# W5500_shield.net
KiCad netlist of a schematic drawn in EAGLE
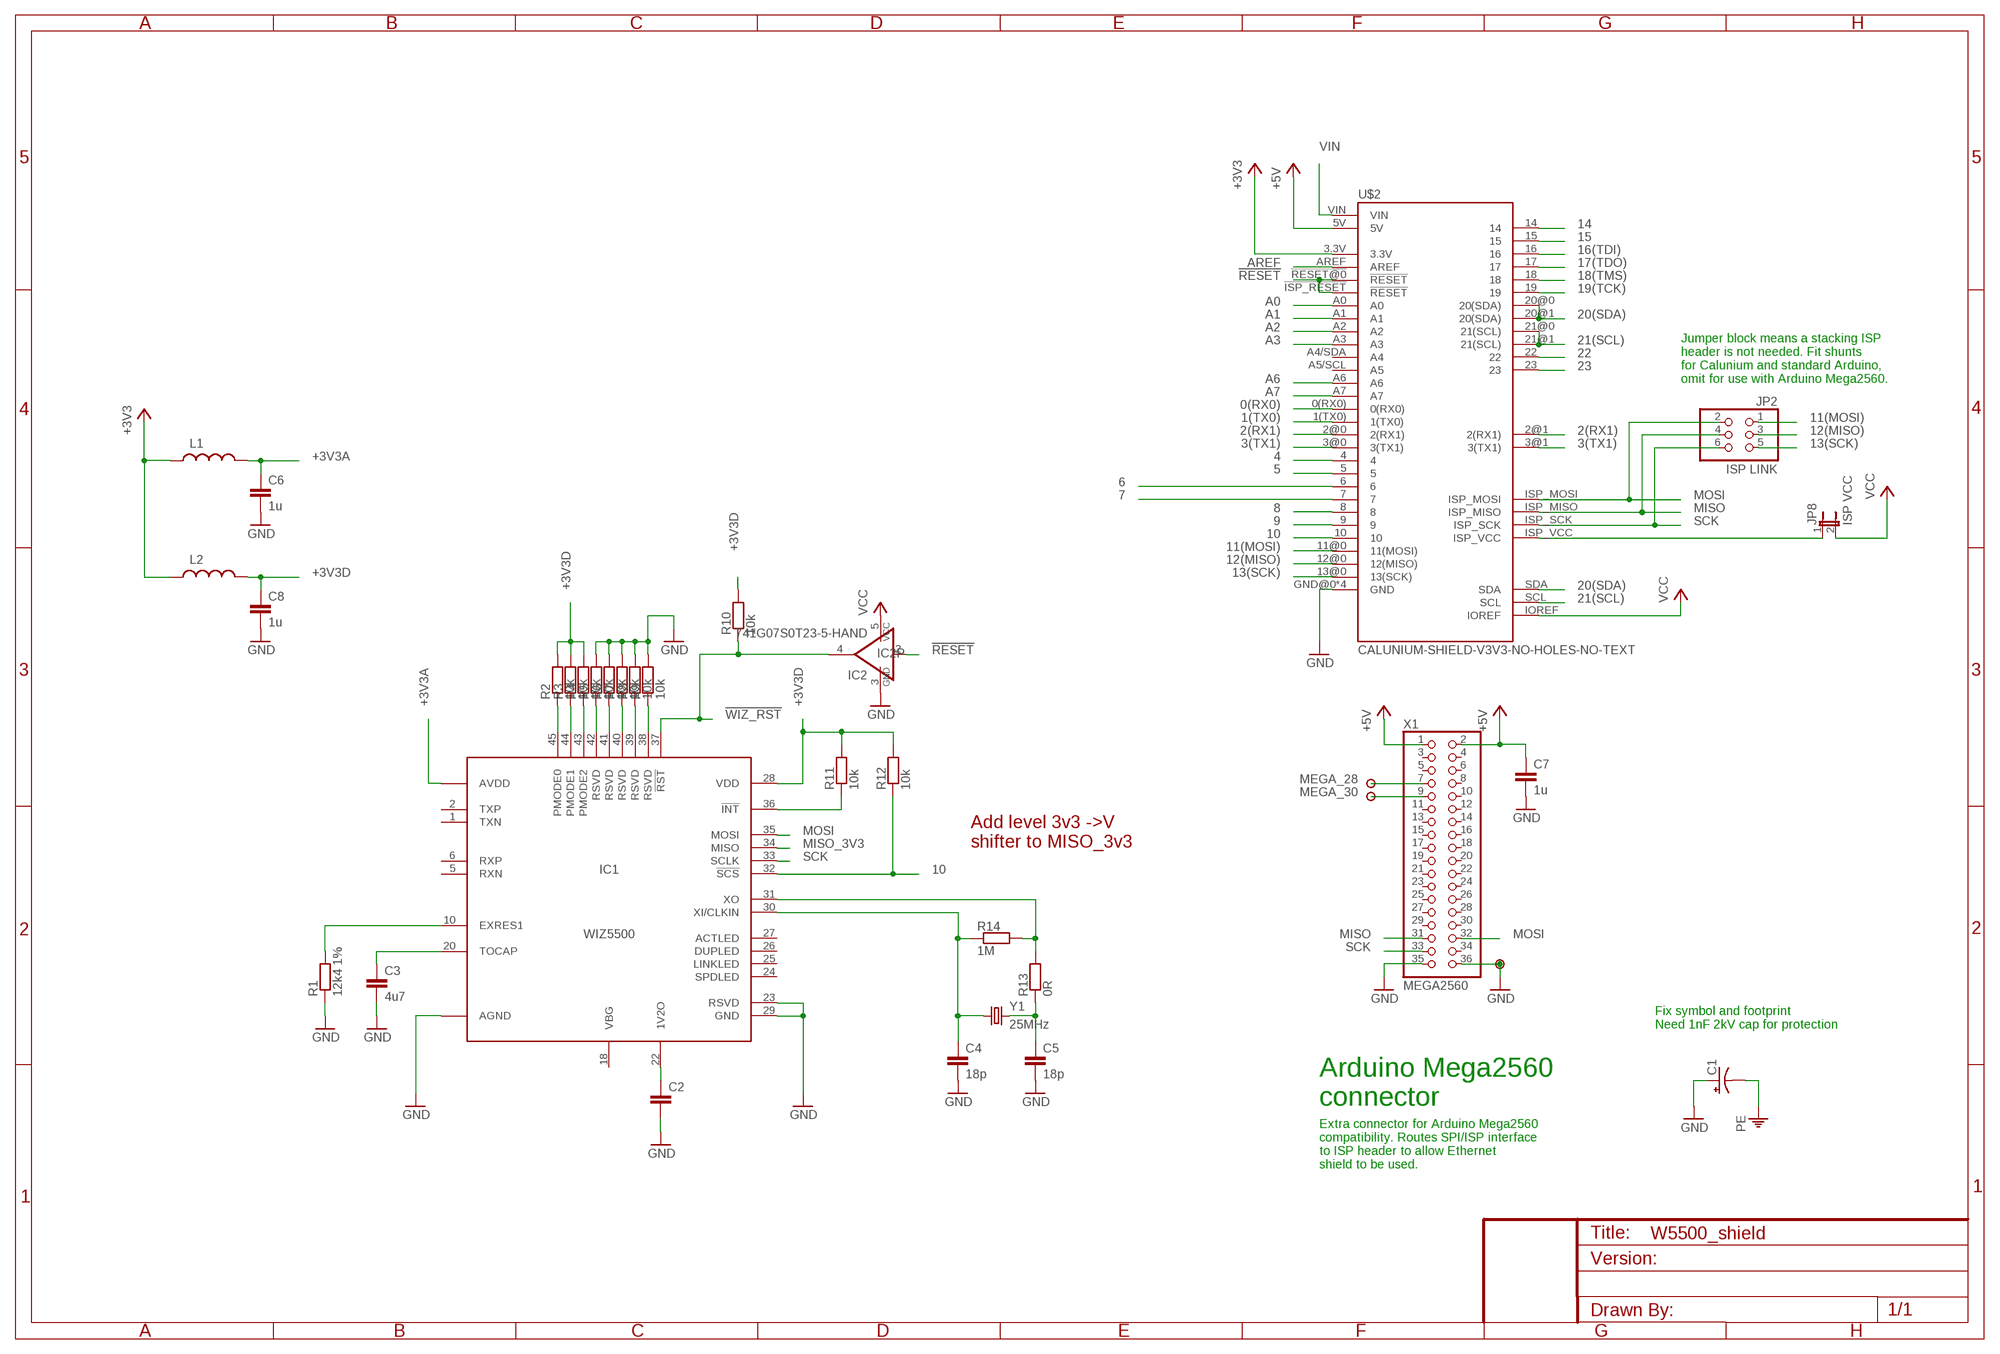
[diagram p0: schematic, sheet 1]

(export (version "E")
  (design (tool "Eeschema 10.0.6"))
  (components
    (comp (ref "C1")
      (value "CAP_POL")
      (footprint "eagle-import:CPOL-RADIAL-100UF-25V-150MIL")
      (libsource (lib "eagle-import") (part "CAP_POL"))
    )
    (comp (ref "C2")
      (value "C-EU1206-HAND")
      (footprint "eagle-import:1206-HAND")
      (libsource (lib "eagle-import") (part "C-EU1206-HAND"))
    )
    (comp (ref "C3")
      (value "4u7")
      (footprint "eagle-import:1206-HAND")
      (libsource (lib "eagle-import") (part "C-EU1206-HAND"))
    )
    (comp (ref "C4")
      (value "18p")
      (footprint "eagle-import:1206-HAND")
      (libsource (lib "eagle-import") (part "C-EU1206-HAND"))
    )
    (comp (ref "C5")
      (value "18p")
      (footprint "eagle-import:1206-HAND")
      (libsource (lib "eagle-import") (part "C-EU1206-HAND"))
    )
    (comp (ref "C6")
      (value "1u")
      (footprint "eagle-import:1206-HAND")
      (libsource (lib "eagle-import") (part "C-EU1206-HAND"))
    )
    (comp (ref "C7")
      (value "1u")
      (footprint "eagle-import:1206-HAND")
      (libsource (lib "eagle-import") (part "C-EU1206-HAND"))
    )
    (comp (ref "C8")
      (value "1u")
      (footprint "eagle-import:1206-HAND")
      (libsource (lib "eagle-import") (part "C-EU1206-HAND"))
    )
    (comp (ref "IC1")
      (value "WIZ5500")
      (footprint "eagle-import:LQFP48-HAND")
      (libsource (lib "eagle-import") (part "WIZNET_W5500"))
    )
    (comp (ref "IC2")
      (value "741G07S0T23-5-HAND")
      (footprint "eagle-import:SOT23-5-HAND")
      (libsource (lib "eagle-import") (part "741G07S0T23-5-HAND"))
    )
    (comp (ref "JP2")
      (value "ISP LINK")
      (footprint "eagle-import:2X03")
      (libsource (lib "eagle-import") (part "PINHD-2X3"))
    )
    (comp (ref "JP8")
      (value "ISP VCC")
      (footprint "eagle-import:1X02")
      (libsource (lib "eagle-import") (part "JUMPER-2PTH"))
    )
    (comp (ref "L1")
      (value "INDUCTOR0805-HAND")
      (footprint "eagle-import:0805-HAND")
      (libsource (lib "eagle-import") (part "INDUCTOR0805-HAND"))
    )
    (comp (ref "L2")
      (value "INDUCTOR0805-HAND")
      (footprint "eagle-import:0805-HAND")
      (libsource (lib "eagle-import") (part "INDUCTOR0805-HAND"))
    )
    (comp (ref "R1")
      (value "12k4 1%")
      (footprint "eagle-import:1206-HAND")
      (libsource (lib "eagle-import") (part "RESISTOR1206-HAND"))
    )
    (comp (ref "R2")
      (value "10k")
      (footprint "eagle-import:1206-HAND")
      (libsource (lib "eagle-import") (part "RESISTOR1206-HAND"))
    )
    (comp (ref "R3")
      (value "10k")
      (footprint "eagle-import:1206-HAND")
      (libsource (lib "eagle-import") (part "RESISTOR1206-HAND"))
    )
    (comp (ref "R4")
      (value "10k")
      (footprint "eagle-import:1206-HAND")
      (libsource (lib "eagle-import") (part "RESISTOR1206-HAND"))
    )
    (comp (ref "R5")
      (value "10k")
      (footprint "eagle-import:1206-HAND")
      (libsource (lib "eagle-import") (part "RESISTOR1206-HAND"))
    )
    (comp (ref "R6")
      (value "10k")
      (footprint "eagle-import:1206-HAND")
      (libsource (lib "eagle-import") (part "RESISTOR1206-HAND"))
    )
    (comp (ref "R7")
      (value "10k")
      (footprint "eagle-import:1206-HAND")
      (libsource (lib "eagle-import") (part "RESISTOR1206-HAND"))
    )
    (comp (ref "R8")
      (value "10k")
      (footprint "eagle-import:1206-HAND")
      (libsource (lib "eagle-import") (part "RESISTOR1206-HAND"))
    )
    (comp (ref "R9")
      (value "10k")
      (footprint "eagle-import:1206-HAND")
      (libsource (lib "eagle-import") (part "RESISTOR1206-HAND"))
    )
    (comp (ref "R10")
      (value "10k")
      (footprint "eagle-import:1206-HAND")
      (libsource (lib "eagle-import") (part "RESISTOR1206-HAND"))
    )
    (comp (ref "R11")
      (value "10k")
      (footprint "eagle-import:1206-HAND")
      (libsource (lib "eagle-import") (part "RESISTOR1206-HAND"))
    )
    (comp (ref "R12")
      (value "10k")
      (footprint "eagle-import:1206-HAND")
      (libsource (lib "eagle-import") (part "RESISTOR1206-HAND"))
    )
    (comp (ref "R13")
      (value "0R")
      (footprint "eagle-import:1206-HAND")
      (libsource (lib "eagle-import") (part "RESISTOR1206-HAND"))
    )
    (comp (ref "R14")
      (value "1M")
      (footprint "eagle-import:1206-HAND")
      (libsource (lib "eagle-import") (part "RESISTOR1206-HAND"))
    )
    (comp (ref "U$2")
      (value "CALUNIUM-SHIELD-V3V3-NO-HOLES-NO-TEXT")
      (footprint "eagle-import:CALUNIUM-SHIELD-NO-OUTLINE-NO-HOLES-NO-TEXT-V3")
      (libsource (lib "eagle-import") (part "CALUNIUM-SHIELD-V3V3-NO-HOLES-NO-TEXT"))
    )
    (comp (ref "U$14")
      (value "PAD")
      (footprint "eagle-import:PAD")
      (libsource (lib "eagle-import") (part "PAD"))
    )
    (comp (ref "U$15")
      (value "PAD")
      (footprint "eagle-import:PAD")
      (libsource (lib "eagle-import") (part "PAD"))
    )
    (comp (ref "U$17")
      (value "PAD")
      (footprint "eagle-import:PAD")
      (libsource (lib "eagle-import") (part "PAD"))
    )
    (comp (ref "X1")
      (value "MEGA2560")
      (footprint "eagle-import:2X18")
      (libsource (lib "eagle-import") (part "PINHD-2X18"))
    )
    (comp (ref "Y1")
      (value "25MHz")
      (footprint "eagle-import:HC49U-V")
      (libsource (lib "eagle-import") (part "CRYSTALHC49UV"))
    )
  )
  (nets
    (net (code "1") (name "+3V3") (class "Default")
      (node (ref "L1") (pin "1") (pinfunction "1_1") (pintype "passive"))
      (node (ref "L2") (pin "1") (pinfunction "1_1") (pintype "passive"))
      (node (ref "U$2") (pin "3.3V") (pinfunction "3.3V_3.3V") (pintype "bidirectional"))
    )
    (net (code "2") (name "+5V") (class "Default")
      (node (ref "C7") (pin "1") (pinfunction "1_1") (pintype "passive"))
      (node (ref "U$2") (pin "5V") (pinfunction "5V_5V") (pintype "bidirectional"))
      (node (ref "X1") (pin "1") (pinfunction "1_1") (pintype "passive"))
      (node (ref "X1") (pin "2") (pinfunction "2_2") (pintype "passive"))
    )
    (net (code "3") (name "/+3V3A") (class "Default")
      (node (ref "C6") (pin "1") (pinfunction "1_1") (pintype "passive"))
      (node (ref "IC1") (pin "11") (pinfunction "AVDD_11") (pintype "power_in"))
      (node (ref "IC1") (pin "15") (pinfunction "AVDD_15") (pintype "power_in"))
      (node (ref "IC1") (pin "17") (pinfunction "AVDD_17") (pintype "power_in"))
      (node (ref "IC1") (pin "21") (pinfunction "AVDD_21") (pintype "power_in"))
      (node (ref "IC1") (pin "4") (pinfunction "AVDD_4") (pintype "power_in"))
      (node (ref "IC1") (pin "8") (pinfunction "AVDD_8") (pintype "power_in"))
      (node (ref "L1") (pin "2") (pinfunction "2_2") (pintype "passive"))
    )
    (net (code "4") (name "/+3V3D") (class "Default")
      (node (ref "C8") (pin "1") (pinfunction "1_1") (pintype "passive"))
      (node (ref "IC1") (pin "28") (pinfunction "VDD_28") (pintype "power_in"))
      (node (ref "L2") (pin "2") (pinfunction "2_2") (pintype "passive"))
      (node (ref "R10") (pin "2") (pinfunction "2_2") (pintype "passive"))
      (node (ref "R11") (pin "2") (pinfunction "2_2") (pintype "passive"))
      (node (ref "R12") (pin "2") (pinfunction "2_2") (pintype "passive"))
      (node (ref "R2") (pin "2") (pinfunction "2_2") (pintype "passive"))
      (node (ref "R3") (pin "2") (pinfunction "2_2") (pintype "passive"))
      (node (ref "R4") (pin "2") (pinfunction "2_2") (pintype "passive"))
    )
    (net (code "5") (name "/0(RX0)") (class "Default")
      (node (ref "U$2") (pin "0(RX0)") (pinfunction "0(RX0)_0(RX0)") (pintype "bidirectional"))
    )
    (net (code "6") (name "/1(TX0)") (class "Default")
      (node (ref "U$2") (pin "1(TX0)") (pinfunction "1(TX0)_1(TX0)") (pintype "bidirectional"))
    )
    (net (code "7") (name "/2(RX1)") (class "Default")
      (node (ref "U$2") (pin "2@0") (pinfunction "2(RX1)_2@0") (pintype "bidirectional"))
      (node (ref "U$2") (pin "2@1") (pinfunction "2(RX1)_2@1") (pintype "bidirectional"))
    )
    (net (code "8") (name "/3(TX1)") (class "Default")
      (node (ref "U$2") (pin "3@0") (pinfunction "3(TX1)_3@0") (pintype "bidirectional"))
      (node (ref "U$2") (pin "3@1") (pinfunction "3(TX1)_3@1") (pintype "bidirectional"))
    )
    (net (code "9") (name "/4") (class "Default")
      (node (ref "U$2") (pin "4") (pinfunction "4_4") (pintype "bidirectional"))
    )
    (net (code "10") (name "/5") (class "Default")
      (node (ref "U$2") (pin "5") (pinfunction "5_5") (pintype "bidirectional"))
    )
    (net (code "11") (name "/6") (class "Default")
      (node (ref "U$2") (pin "6") (pinfunction "6_6") (pintype "bidirectional"))
    )
    (net (code "12") (name "/7") (class "Default")
      (node (ref "U$2") (pin "7") (pinfunction "7_7") (pintype "bidirectional"))
    )
    (net (code "13") (name "/8") (class "Default")
      (node (ref "U$2") (pin "8") (pinfunction "8_8") (pintype "bidirectional"))
    )
    (net (code "14") (name "/9") (class "Default")
      (node (ref "U$2") (pin "9") (pinfunction "9_9") (pintype "bidirectional"))
    )
    (net (code "15") (name "/10") (class "Default")
      (node (ref "IC1") (pin "32") (pinfunction "~{SCS}_32") (pintype "output"))
      (node (ref "R12") (pin "1") (pinfunction "1_1") (pintype "passive"))
      (node (ref "U$2") (pin "10") (pinfunction "10_10") (pintype "bidirectional"))
    )
    (net (code "16") (name "/11(MOSI)") (class "Default")
      (node (ref "JP2") (pin "1") (pinfunction "1_1") (pintype "passive"))
      (node (ref "U$2") (pin "11@0") (pinfunction "11(MOSI)_11@0") (pintype "bidirectional"))
    )
    (net (code "17") (name "/12(MISO)") (class "Default")
      (node (ref "JP2") (pin "3") (pinfunction "3_3") (pintype "passive"))
      (node (ref "U$2") (pin "12@0") (pinfunction "12(MISO)_12@0") (pintype "bidirectional"))
    )
    (net (code "18") (name "/13(SCK)") (class "Default")
      (node (ref "JP2") (pin "5") (pinfunction "5_5") (pintype "passive"))
      (node (ref "U$2") (pin "13@0") (pinfunction "13(SCK)_13@0") (pintype "bidirectional"))
    )
    (net (code "19") (name "/14") (class "Default")
      (node (ref "U$2") (pin "14") (pinfunction "14_14") (pintype "bidirectional"))
    )
    (net (code "20") (name "/15") (class "Default")
      (node (ref "U$2") (pin "15") (pinfunction "15_15") (pintype "bidirectional"))
    )
    (net (code "21") (name "/16(TDI)") (class "Default")
      (node (ref "U$2") (pin "16") (pinfunction "16_16") (pintype "bidirectional"))
    )
    (net (code "22") (name "/17(TDO)") (class "Default")
      (node (ref "U$2") (pin "17") (pinfunction "17_17") (pintype "bidirectional"))
    )
    (net (code "23") (name "/18(TMS)") (class "Default")
      (node (ref "U$2") (pin "18") (pinfunction "18_18") (pintype "bidirectional"))
    )
    (net (code "24") (name "/19(TCK)") (class "Default")
      (node (ref "U$2") (pin "19") (pinfunction "19_19") (pintype "bidirectional"))
    )
    (net (code "25") (name "/20(SDA)") (class "Default")
      (node (ref "U$2") (pin "20@0") (pinfunction "20(SDA)_20@0") (pintype "bidirectional"))
      (node (ref "U$2") (pin "20@1") (pinfunction "20(SDA)_20@1") (pintype "bidirectional"))
      (node (ref "U$2") (pin "SDA") (pinfunction "SDA_SDA") (pintype "bidirectional"))
    )
    (net (code "26") (name "/21(SCL)") (class "Default")
      (node (ref "U$2") (pin "21@0") (pinfunction "21(SCL)_21@0") (pintype "bidirectional"))
      (node (ref "U$2") (pin "21@1") (pinfunction "21(SCL)_21@1") (pintype "bidirectional"))
      (node (ref "U$2") (pin "SCL") (pinfunction "SCL_SCL") (pintype "bidirectional"))
    )
    (net (code "27") (name "/22") (class "Default")
      (node (ref "U$2") (pin "22") (pinfunction "22_22") (pintype "bidirectional"))
    )
    (net (code "28") (name "/23") (class "Default")
      (node (ref "U$2") (pin "23") (pinfunction "23_23") (pintype "bidirectional"))
    )
    (net (code "29") (name "/A0") (class "Default")
      (node (ref "U$2") (pin "A0") (pinfunction "A0_A0") (pintype "bidirectional"))
    )
    (net (code "30") (name "/A1") (class "Default")
      (node (ref "U$2") (pin "A1") (pinfunction "A1_A1") (pintype "bidirectional"))
    )
    (net (code "31") (name "/A2") (class "Default")
      (node (ref "U$2") (pin "A2") (pinfunction "A2_A2") (pintype "bidirectional"))
    )
    (net (code "32") (name "/A3") (class "Default")
      (node (ref "U$2") (pin "A3") (pinfunction "A3_A3") (pintype "bidirectional"))
    )
    (net (code "33") (name "/A6") (class "Default")
      (node (ref "U$2") (pin "A6") (pinfunction "A6_A6") (pintype "bidirectional"))
    )
    (net (code "34") (name "/A7") (class "Default")
      (node (ref "U$2") (pin "A7") (pinfunction "A7_A7") (pintype "bidirectional"))
    )
    (net (code "35") (name "/AREF") (class "Default")
      (node (ref "U$2") (pin "AREF") (pinfunction "AREF_AREF") (pintype "bidirectional"))
    )
    (net (code "36") (name "/MEGA_28") (class "Default")
      (node (ref "U$14") (pin "1") (pinfunction "1_1") (pintype "bidirectional"))
      (node (ref "X1") (pin "7") (pinfunction "7_7") (pintype "passive"))
    )
    (net (code "37") (name "/MEGA_30") (class "Default")
      (node (ref "U$15") (pin "1") (pinfunction "1_1") (pintype "bidirectional"))
      (node (ref "X1") (pin "9") (pinfunction "9_9") (pintype "passive"))
    )
    (net (code "38") (name "/MISO") (class "Default")
      (node (ref "JP2") (pin "4") (pinfunction "4_4") (pintype "passive"))
      (node (ref "U$2") (pin "ISP_MISO") (pinfunction "ISP_MISO_ISP_MISO") (pintype "bidirectional"))
      (node (ref "X1") (pin "31") (pinfunction "31_31") (pintype "passive"))
    )
    (net (code "39") (name "/MISO_3V3") (class "Default")
      (node (ref "IC1") (pin "34") (pinfunction "MISO_34") (pintype "output"))
    )
    (net (code "40") (name "/MOSI") (class "Default")
      (node (ref "IC1") (pin "35") (pinfunction "MOSI_35") (pintype "input"))
      (node (ref "JP2") (pin "2") (pinfunction "2_2") (pintype "passive"))
      (node (ref "U$2") (pin "ISP_MOSI") (pinfunction "ISP_MOSI_ISP_MOSI") (pintype "bidirectional"))
      (node (ref "X1") (pin "32") (pinfunction "32_32") (pintype "passive"))
    )
    (net (code "41") (name "/SCK") (class "Default")
      (node (ref "IC1") (pin "33") (pinfunction "SCLK_33") (pintype "input"))
      (node (ref "JP2") (pin "6") (pinfunction "6_6") (pintype "passive"))
      (node (ref "U$2") (pin "ISP_SCK") (pinfunction "ISP_SCK_ISP_SCK") (pintype "bidirectional"))
      (node (ref "X1") (pin "33") (pinfunction "33_33") (pintype "passive"))
    )
    (net (code "42") (name "/VIN") (class "Default")
      (node (ref "U$2") (pin "VIN") (pinfunction "VIN_VIN") (pintype "bidirectional"))
    )
    (net (code "43") (name "/~{RESET}") (class "Default")
      (node (ref "IC2") (pin "2") (pinfunction "I_2") (pintype "input"))
      (node (ref "U$2") (pin "!ISP_RESET") (pinfunction "~{RESET}_!ISP_RESET") (pintype "bidirectional"))
      (node (ref "U$2") (pin "!RESET@0") (pinfunction "~{RESET}_!RESET@0") (pintype "bidirectional"))
    )
    (net (code "44") (name "/~{WIZ_RST}") (class "Default")
      (node (ref "IC1") (pin "37") (pinfunction "~{RST}_37") (pintype "input"))
      (node (ref "IC2") (pin "4") (pinfunction "O_4") (pintype "open_collector"))
      (node (ref "R10") (pin "1") (pinfunction "1_1") (pintype "passive"))
    )
    (net (code "45") (name "GND") (class "Default")
      (node (ref "C1") (pin "1") (pinfunction "+_1") (pintype "passive"))
      (node (ref "C2") (pin "2") (pinfunction "2_2") (pintype "passive"))
      (node (ref "C3") (pin "2") (pinfunction "2_2") (pintype "passive"))
      (node (ref "C4") (pin "2") (pinfunction "2_2") (pintype "passive"))
      (node (ref "C5") (pin "2") (pinfunction "2_2") (pintype "passive"))
      (node (ref "C6") (pin "2") (pinfunction "2_2") (pintype "passive"))
      (node (ref "C7") (pin "2") (pinfunction "2_2") (pintype "passive"))
      (node (ref "C8") (pin "2") (pinfunction "2_2") (pintype "passive"))
      (node (ref "IC1") (pin "14") (pinfunction "AGND_14") (pintype "power_in"))
      (node (ref "IC1") (pin "16") (pinfunction "AGND_16") (pintype "power_in"))
      (node (ref "IC1") (pin "19") (pinfunction "AGND_19") (pintype "power_in"))
      (node (ref "IC1") (pin "23") (pinfunction "RSVD_23") (pintype "input"))
      (node (ref "IC1") (pin "29") (pinfunction "GND_29") (pintype "power_in"))
      (node (ref "IC1") (pin "3") (pinfunction "AGND_3") (pintype "power_in"))
      (node (ref "IC1") (pin "48") (pinfunction "AGND_48") (pintype "power_in"))
      (node (ref "IC1") (pin "9") (pinfunction "AGND_9") (pintype "power_in"))
      (node (ref "IC2") (pin "3") (pinfunction "GND_3") (pintype "power_in"))
      (node (ref "R1") (pin "1") (pinfunction "1_1") (pintype "passive"))
      (node (ref "R5") (pin "2") (pinfunction "2_2") (pintype "passive"))
      (node (ref "R6") (pin "2") (pinfunction "2_2") (pintype "passive"))
      (node (ref "R7") (pin "2") (pinfunction "2_2") (pintype "passive"))
      (node (ref "R8") (pin "2") (pinfunction "2_2") (pintype "passive"))
      (node (ref "R9") (pin "2") (pinfunction "2_2") (pintype "passive"))
      (node (ref "U$17") (pin "1") (pinfunction "1_1") (pintype "bidirectional"))
      (node (ref "U$2") (pin "GND@0") (pinfunction "GND_GND@0") (pintype "bidirectional"))
      (node (ref "U$2") (pin "GND@1") (pinfunction "GND_GND@1") (pintype "bidirectional"))
      (node (ref "U$2") (pin "GND@2") (pinfunction "GND_GND@2") (pintype "bidirectional"))
      (node (ref "U$2") (pin "GND@3") (pinfunction "GND_GND@3") (pintype "bidirectional"))
      (node (ref "X1") (pin "35") (pinfunction "35_35") (pintype "passive"))
      (node (ref "X1") (pin "36") (pinfunction "36_36") (pintype "passive"))
    )
    (net (code "46") (name "Net-(C5-Pad1)") (class "Default")
      (node (ref "C5") (pin "1") (pinfunction "1_1") (pintype "passive"))
      (node (ref "R13") (pin "1") (pinfunction "1_1") (pintype "passive"))
      (node (ref "Y1") (pin "2") (pinfunction "2_2") (pintype "passive"))
    )
    (net (code "47") (name "Net-(IC1-1V2O)") (class "Default")
      (node (ref "C2") (pin "1") (pinfunction "1_1") (pintype "passive"))
      (node (ref "IC1") (pin "22") (pinfunction "1V2O_22") (pintype "output"))
    )
    (net (code "48") (name "Net-(IC1-EXRES1)") (class "Default")
      (node (ref "IC1") (pin "10") (pinfunction "EXRES1_10") (pintype "passive"))
      (node (ref "R1") (pin "2") (pinfunction "2_2") (pintype "passive"))
    )
    (net (code "49") (name "Net-(IC1-PMODE0)") (class "Default")
      (node (ref "IC1") (pin "45") (pinfunction "PMODE0_45") (pintype "input"))
      (node (ref "R2") (pin "1") (pinfunction "1_1") (pintype "passive"))
    )
    (net (code "50") (name "Net-(IC1-PMODE1)") (class "Default")
      (node (ref "IC1") (pin "44") (pinfunction "PMODE1_44") (pintype "input"))
      (node (ref "R3") (pin "1") (pinfunction "1_1") (pintype "passive"))
    )
    (net (code "51") (name "Net-(IC1-PMODE2)") (class "Default")
      (node (ref "IC1") (pin "43") (pinfunction "PMODE2_43") (pintype "input"))
      (node (ref "R4") (pin "1") (pinfunction "1_1") (pintype "passive"))
    )
    (net (code "52") (name "Net-(IC1-RSVD-Pad38)") (class "Default")
      (node (ref "IC1") (pin "38") (pinfunction "RSVD_38") (pintype "input"))
      (node (ref "R9") (pin "1") (pinfunction "1_1") (pintype "passive"))
    )
    (net (code "53") (name "Net-(IC1-RSVD-Pad39)") (class "Default")
      (node (ref "IC1") (pin "39") (pinfunction "RSVD_39") (pintype "input"))
      (node (ref "R8") (pin "1") (pinfunction "1_1") (pintype "passive"))
    )
    (net (code "54") (name "Net-(IC1-RSVD-Pad40)") (class "Default")
      (node (ref "IC1") (pin "40") (pinfunction "RSVD_40") (pintype "input"))
      (node (ref "R7") (pin "1") (pinfunction "1_1") (pintype "passive"))
    )
    (net (code "55") (name "Net-(IC1-RSVD-Pad41)") (class "Default")
      (node (ref "IC1") (pin "41") (pinfunction "RSVD_41") (pintype "input"))
      (node (ref "R6") (pin "1") (pinfunction "1_1") (pintype "passive"))
    )
    (net (code "56") (name "Net-(IC1-RSVD-Pad42)") (class "Default")
      (node (ref "IC1") (pin "42") (pinfunction "RSVD_42") (pintype "input"))
      (node (ref "R5") (pin "1") (pinfunction "1_1") (pintype "passive"))
    )
    (net (code "57") (name "Net-(IC1-TOCAP)") (class "Default")
      (node (ref "C3") (pin "1") (pinfunction "1_1") (pintype "passive"))
      (node (ref "IC1") (pin "20") (pinfunction "TOCAP_20") (pintype "passive"))
    )
    (net (code "58") (name "Net-(IC1-XI{slash}CLKIN)") (class "Default")
      (node (ref "C4") (pin "1") (pinfunction "1_1") (pintype "passive"))
      (node (ref "IC1") (pin "30") (pinfunction "XI/CLKIN_30") (pintype "output"))
      (node (ref "R14") (pin "1") (pinfunction "1_1") (pintype "passive"))
      (node (ref "Y1") (pin "1") (pinfunction "1_1") (pintype "passive"))
    )
    (net (code "59") (name "Net-(IC1-XO)") (class "Default")
      (node (ref "IC1") (pin "31") (pinfunction "XO_31") (pintype "output"))
      (node (ref "R13") (pin "2") (pinfunction "2_2") (pintype "passive"))
      (node (ref "R14") (pin "2") (pinfunction "2_2") (pintype "passive"))
    )
    (net (code "60") (name "Net-(IC1-~{INT})") (class "Default")
      (node (ref "IC1") (pin "36") (pinfunction "~{INT}_36") (pintype "output"))
      (node (ref "R11") (pin "1") (pinfunction "1_1") (pintype "passive"))
    )
    (net (code "61") (name "Net-(JP8-Pad1)") (class "Default")
      (node (ref "JP8") (pin "1") (pinfunction "1_1") (pintype "passive"))
      (node (ref "U$2") (pin "ISP_VCC") (pinfunction "ISP_VCC_ISP_VCC") (pintype "bidirectional"))
    )
    (net (code "62") (name "PE") (class "Default")
      (node (ref "C1") (pin "2") (pinfunction "-_2") (pintype "passive"))
    )
    (net (code "63") (name "VCC") (class "Default")
      (node (ref "IC2") (pin "5") (pinfunction "VCC_5") (pintype "power_in"))
      (node (ref "JP8") (pin "2") (pinfunction "2_2") (pintype "passive"))
      (node (ref "U$2") (pin "IOREF") (pinfunction "IOREF_IOREF") (pintype "bidirectional"))
    )
    (net (code "64") (name "unconnected-(IC1-ACTLED-Pad27)") (class "Default")
      (node (ref "IC1") (pin "27") (pinfunction "ACTLED_27") (pintype "output"))
    )
    (net (code "65") (name "unconnected-(IC1-DUPLED-Pad26)") (class "Default")
      (node (ref "IC1") (pin "26") (pinfunction "DUPLED_26") (pintype "output"))
    )
    (net (code "66") (name "unconnected-(IC1-LINKLED-Pad25)") (class "Default")
      (node (ref "IC1") (pin "25") (pinfunction "LINKLED_25") (pintype "output"))
    )
    (net (code "67") (name "unconnected-(IC1-RXN-Pad5)") (class "Default")
      (node (ref "IC1") (pin "5") (pinfunction "RXN_5") (pintype "input"))
    )
    (net (code "68") (name "unconnected-(IC1-RXP-Pad6)") (class "Default")
      (node (ref "IC1") (pin "6") (pinfunction "RXP_6") (pintype "input"))
    )
    (net (code "69") (name "unconnected-(IC1-SPDLED-Pad24)") (class "Default")
      (node (ref "IC1") (pin "24") (pinfunction "SPDLED_24") (pintype "output"))
    )
    (net (code "70") (name "unconnected-(IC1-TXN-Pad1)") (class "Default")
      (node (ref "IC1") (pin "1") (pinfunction "TXN_1") (pintype "output"))
    )
    (net (code "71") (name "unconnected-(IC1-TXP-Pad2)") (class "Default")
      (node (ref "IC1") (pin "2") (pinfunction "TXP_2") (pintype "output"))
    )
    (net (code "72") (name "unconnected-(IC1-VBG-Pad18)") (class "Default")
      (node (ref "IC1") (pin "18") (pinfunction "VBG_18") (pintype "no_connect"))
    )
    (net (code "73") (name "unconnected-(U$2-A4-PadA4{slash}SDA)") (class "Default")
      (node (ref "U$2") (pin "A4/SDA") (pinfunction "A4_A4/SDA") (pintype "bidirectional"))
    )
    (net (code "74") (name "unconnected-(U$2-A5-PadA5{slash}SCL)") (class "Default")
      (node (ref "U$2") (pin "A5/SCL") (pinfunction "A5_A5/SCL") (pintype "bidirectional"))
    )
    (net (code "75") (name "unconnected-(X1-Pad3)") (class "Default")
      (node (ref "X1") (pin "3") (pinfunction "3_3") (pintype "passive"))
    )
    (net (code "76") (name "unconnected-(X1-Pad4)") (class "Default")
      (node (ref "X1") (pin "4") (pinfunction "4_4") (pintype "passive"))
    )
    (net (code "77") (name "unconnected-(X1-Pad5)") (class "Default")
      (node (ref "X1") (pin "5") (pinfunction "5_5") (pintype "passive"))
    )
    (net (code "78") (name "unconnected-(X1-Pad6)") (class "Default")
      (node (ref "X1") (pin "6") (pinfunction "6_6") (pintype "passive"))
    )
    (net (code "79") (name "unconnected-(X1-Pad8)") (class "Default")
      (node (ref "X1") (pin "8") (pinfunction "8_8") (pintype "passive"))
    )
    (net (code "80") (name "unconnected-(X1-Pad10)") (class "Default")
      (node (ref "X1") (pin "10") (pinfunction "10_10") (pintype "passive"))
    )
    (net (code "81") (name "unconnected-(X1-Pad11)") (class "Default")
      (node (ref "X1") (pin "11") (pinfunction "11_11") (pintype "passive"))
    )
    (net (code "82") (name "unconnected-(X1-Pad12)") (class "Default")
      (node (ref "X1") (pin "12") (pinfunction "12_12") (pintype "passive"))
    )
    (net (code "83") (name "unconnected-(X1-Pad13)") (class "Default")
      (node (ref "X1") (pin "13") (pinfunction "13_13") (pintype "passive"))
    )
    (net (code "84") (name "unconnected-(X1-Pad14)") (class "Default")
      (node (ref "X1") (pin "14") (pinfunction "14_14") (pintype "passive"))
    )
    (net (code "85") (name "unconnected-(X1-Pad15)") (class "Default")
      (node (ref "X1") (pin "15") (pinfunction "15_15") (pintype "passive"))
    )
    (net (code "86") (name "unconnected-(X1-Pad16)") (class "Default")
      (node (ref "X1") (pin "16") (pinfunction "16_16") (pintype "passive"))
    )
    (net (code "87") (name "unconnected-(X1-Pad17)") (class "Default")
      (node (ref "X1") (pin "17") (pinfunction "17_17") (pintype "passive"))
    )
    (net (code "88") (name "unconnected-(X1-Pad18)") (class "Default")
      (node (ref "X1") (pin "18") (pinfunction "18_18") (pintype "passive"))
    )
    (net (code "89") (name "unconnected-(X1-Pad19)") (class "Default")
      (node (ref "X1") (pin "19") (pinfunction "19_19") (pintype "passive"))
    )
    (net (code "90") (name "unconnected-(X1-Pad20)") (class "Default")
      (node (ref "X1") (pin "20") (pinfunction "20_20") (pintype "passive"))
    )
    (net (code "91") (name "unconnected-(X1-Pad21)") (class "Default")
      (node (ref "X1") (pin "21") (pinfunction "21_21") (pintype "passive"))
    )
    (net (code "92") (name "unconnected-(X1-Pad22)") (class "Default")
      (node (ref "X1") (pin "22") (pinfunction "22_22") (pintype "passive"))
    )
    (net (code "93") (name "unconnected-(X1-Pad23)") (class "Default")
      (node (ref "X1") (pin "23") (pinfunction "23_23") (pintype "passive"))
    )
    (net (code "94") (name "unconnected-(X1-Pad24)") (class "Default")
      (node (ref "X1") (pin "24") (pinfunction "24_24") (pintype "passive"))
    )
    (net (code "95") (name "unconnected-(X1-Pad25)") (class "Default")
      (node (ref "X1") (pin "25") (pinfunction "25_25") (pintype "passive"))
    )
    (net (code "96") (name "unconnected-(X1-Pad26)") (class "Default")
      (node (ref "X1") (pin "26") (pinfunction "26_26") (pintype "passive"))
    )
    (net (code "97") (name "unconnected-(X1-Pad27)") (class "Default")
      (node (ref "X1") (pin "27") (pinfunction "27_27") (pintype "passive"))
    )
    (net (code "98") (name "unconnected-(X1-Pad28)") (class "Default")
      (node (ref "X1") (pin "28") (pinfunction "28_28") (pintype "passive"))
    )
    (net (code "99") (name "unconnected-(X1-Pad29)") (class "Default")
      (node (ref "X1") (pin "29") (pinfunction "29_29") (pintype "passive"))
    )
    (net (code "100") (name "unconnected-(X1-Pad30)") (class "Default")
      (node (ref "X1") (pin "30") (pinfunction "30_30") (pintype "passive"))
    )
    (net (code "101") (name "unconnected-(X1-Pad34)") (class "Default")
      (node (ref "X1") (pin "34") (pinfunction "34_34") (pintype "passive"))
    )
  )
)
